# Serial_CAN_FD.net
KiCad netlist of a schematic drawn in EAGLE
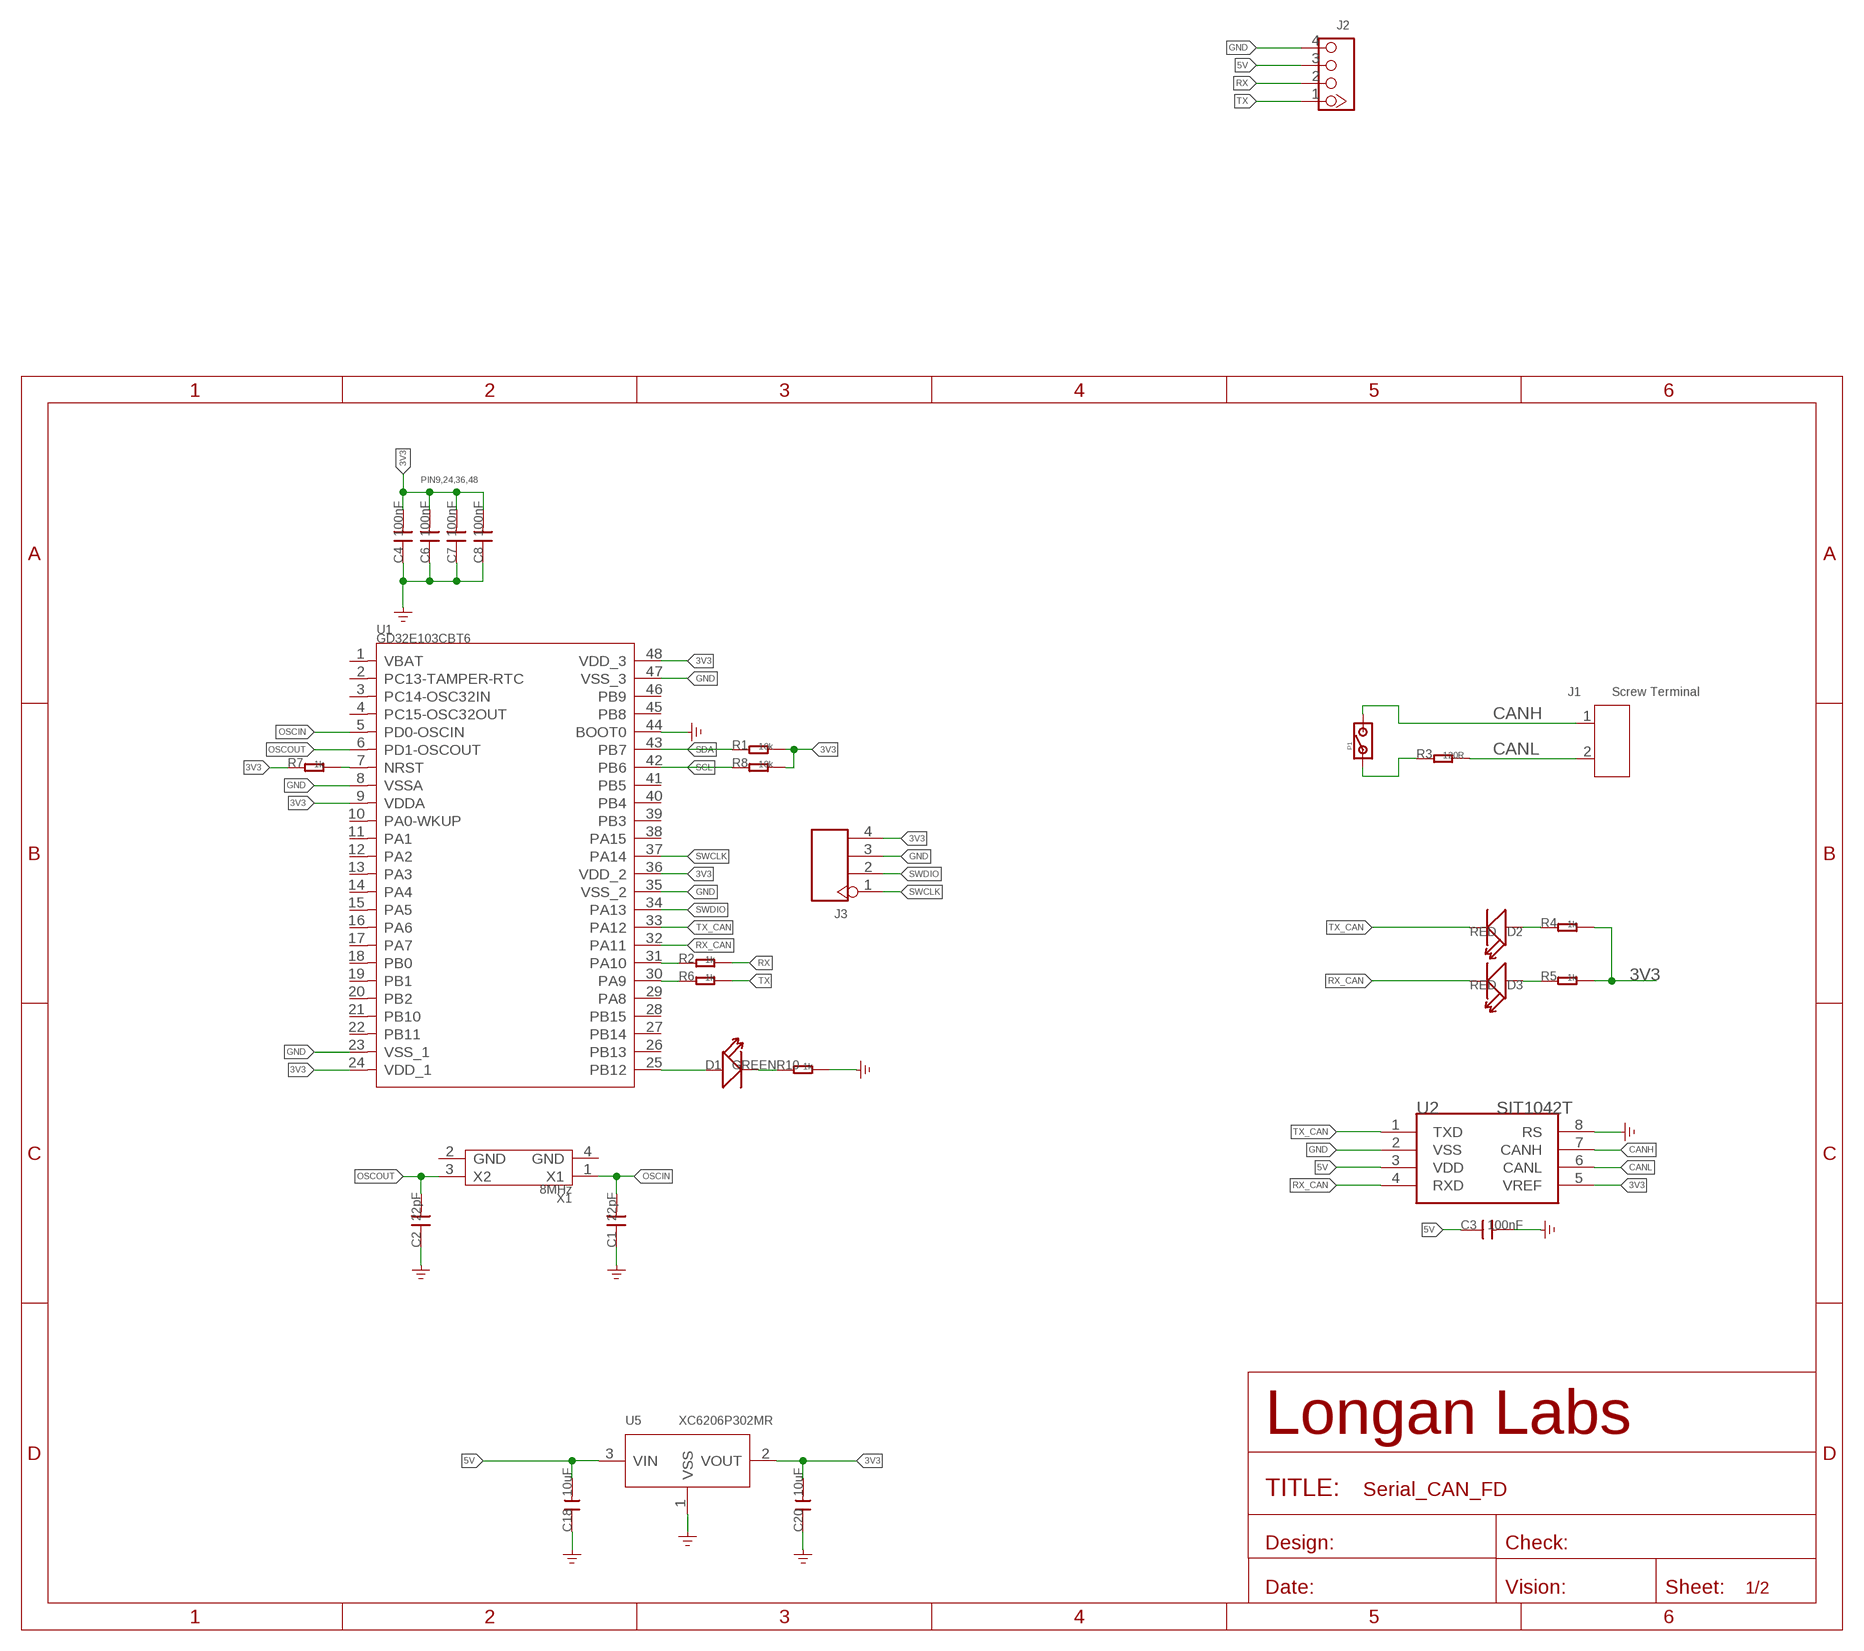
[diagram p0: schematic, sheet 1]

(export (version "E")
  (design (tool "Eeschema 10.0.6"))
  (components
    (comp (ref "C1")
      (value "22pF")
      (footprint "eagle-import:0603")
      (libsource (lib "eagle-import") (part "C-0603"))
    )
    (comp (ref "C2")
      (value "22pF")
      (footprint "eagle-import:0603")
      (libsource (lib "eagle-import") (part "C-0603"))
    )
    (comp (ref "C3")
      (value "100nF")
      (footprint "eagle-import:0603")
      (libsource (lib "eagle-import") (part "C-0603"))
    )
    (comp (ref "C4")
      (value "100nF")
      (footprint "eagle-import:0603")
      (libsource (lib "eagle-import") (part "C-0603"))
    )
    (comp (ref "C6")
      (value "100nF")
      (footprint "eagle-import:0603")
      (libsource (lib "eagle-import") (part "C-0603"))
    )
    (comp (ref "C7")
      (value "100nF")
      (footprint "eagle-import:0603")
      (libsource (lib "eagle-import") (part "C-0603"))
    )
    (comp (ref "C8")
      (value "100nF")
      (footprint "eagle-import:0603")
      (libsource (lib "eagle-import") (part "C-0603"))
    )
    (comp (ref "C18")
      (value "10uF")
      (footprint "eagle-import:C0603")
      (libsource (lib "eagle-import") (part "CAP-0603"))
    )
    (comp (ref "C20")
      (value "10uF")
      (footprint "eagle-import:C0603")
      (libsource (lib "eagle-import") (part "CAP-0603"))
    )
    (comp (ref "D1")
      (value "GREEN")
      (footprint "eagle-import:LED-0603")
      (libsource (lib "eagle-import") (part "LED'0603'"))
    )
    (comp (ref "D2")
      (value "RED")
      (footprint "eagle-import:LED-0603")
      (libsource (lib "eagle-import") (part "LED'0603'"))
    )
    (comp (ref "D3")
      (value "RED")
      (footprint "eagle-import:LED-0603")
      (libsource (lib "eagle-import") (part "LED'0603'"))
    )
    (comp (ref "J1")
      (value "Screw Terminal")
      (footprint "eagle-import:2P-3.5")
      (libsource (lib "eagle-import") (part "SCREW-TERMINAL-2P'3.5'"))
    )
    (comp (ref "J2")
      (value "320110033")
      (footprint "eagle-import:HW4-2.0")
      (libsource (lib "eagle-import") (part "GROVE-CONNECTOR-DIP-320110033"))
    )
    (comp (ref "J3")
      (value "HEADER-4P-65/35MIL")
      (footprint "eagle-import:H4-2.54")
      (libsource (lib "eagle-import") (part "HEADER-4P-65/35MIL"))
    )
    (comp (ref "P1")
      (value "PAD-JUMPER-2P")
      (footprint "eagle-import:2P-SMD-1.78X1.27")
      (libsource (lib "eagle-import") (part "PAD-JUMPER-2P"))
    )
    (comp (ref "R1")
      (value "10k")
      (footprint "eagle-import:0603")
      (libsource (lib "eagle-import") (part "R-0603"))
    )
    (comp (ref "R2")
      (value "1k")
      (footprint "eagle-import:0603")
      (libsource (lib "eagle-import") (part "R-0603"))
    )
    (comp (ref "R3")
      (value "120R")
      (footprint "eagle-import:0603")
      (libsource (lib "eagle-import") (part "R-0603"))
    )
    (comp (ref "R4")
      (value "1k")
      (footprint "eagle-import:0603")
      (libsource (lib "eagle-import") (part "R-0603"))
    )
    (comp (ref "R5")
      (value "1k")
      (footprint "eagle-import:0603")
      (libsource (lib "eagle-import") (part "R-0603"))
    )
    (comp (ref "R6")
      (value "1k")
      (footprint "eagle-import:0603")
      (libsource (lib "eagle-import") (part "R-0603"))
    )
    (comp (ref "R7")
      (value "1k")
      (footprint "eagle-import:0603")
      (libsource (lib "eagle-import") (part "R-0603"))
    )
    (comp (ref "R8")
      (value "10k")
      (footprint "eagle-import:0603")
      (libsource (lib "eagle-import") (part "R-0603"))
    )
    (comp (ref "R10")
      (value "1k")
      (footprint "eagle-import:0603")
      (libsource (lib "eagle-import") (part "R-0603"))
    )
    (comp (ref "U1")
      (value "GD32E103CBT6")
      (footprint "eagle-import:LQFP48")
      (libsource (lib "eagle-import") (part "MCU-GD32E103CBT6"))
    )
    (comp (ref "U2")
      (value "SIT1042T")
      (footprint "eagle-import:SOIC8-6.0")
      (libsource (lib "eagle-import") (part "MCP2551-SOIC8"))
    )
    (comp (ref "U5")
      (value "XC6206P302MR")
      (footprint "eagle-import:SOT-23")
      (libsource (lib "eagle-import") (part "PMIC-XC6206PMR"))
    )
    (comp (ref "X1")
      (value "8MHz")
      (footprint "eagle-import:X4-SMD-3.2X2.5X0.7MM")
      (libsource (lib "eagle-import") (part "CRYSTAL-4P-3225"))
    )
  )
  (nets
    (net (code "1") (name "3V3") (class "Default")
      (node (ref "C20") (pin "2") (pinfunction "2_2") (pintype "passive"))
      (node (ref "C4") (pin "2") (pinfunction "2_2") (pintype "passive"))
      (node (ref "C6") (pin "2") (pinfunction "2_2") (pintype "passive"))
      (node (ref "C7") (pin "2") (pinfunction "2_2") (pintype "passive"))
      (node (ref "C8") (pin "2") (pinfunction "2_2") (pintype "passive"))
      (node (ref "J3") (pin "4") (pinfunction "P$4_4") (pintype "bidirectional"))
      (node (ref "R1") (pin "2") (pinfunction "2_2") (pintype "passive"))
      (node (ref "R4") (pin "2") (pinfunction "2_2") (pintype "passive"))
      (node (ref "R5") (pin "2") (pinfunction "2_2") (pintype "passive"))
      (node (ref "R7") (pin "1") (pinfunction "1_1") (pintype "passive"))
      (node (ref "R8") (pin "2") (pinfunction "2_2") (pintype "passive"))
      (node (ref "U1") (pin "24") (pinfunction "VDD_1_24") (pintype "bidirectional"))
      (node (ref "U1") (pin "36") (pinfunction "VDD_2_36") (pintype "bidirectional"))
      (node (ref "U1") (pin "48") (pinfunction "VDD_3_48") (pintype "bidirectional"))
      (node (ref "U1") (pin "9") (pinfunction "VDDA_9") (pintype "bidirectional"))
      (node (ref "U2") (pin "5") (pinfunction "VREF_5") (pintype "bidirectional"))
      (node (ref "U5") (pin "2") (pinfunction "VOUT_2") (pintype "bidirectional"))
    )
    (net (code "2") (name "5V") (class "Default")
      (node (ref "C18") (pin "2") (pinfunction "2_2") (pintype "passive"))
      (node (ref "C3") (pin "1") (pinfunction "1_1") (pintype "passive"))
      (node (ref "J2") (pin "3") (pinfunction "3_3") (pintype "bidirectional"))
      (node (ref "U2") (pin "3") (pinfunction "VDD_3") (pintype "bidirectional"))
      (node (ref "U5") (pin "3") (pinfunction "VIN_3") (pintype "bidirectional"))
    )
    (net (code "3") (name "CANH") (class "Default")
      (node (ref "J1") (pin "1") (pinfunction "1_1") (pintype "bidirectional"))
      (node (ref "P1") (pin "2") (pinfunction "2_2") (pintype "bidirectional"))
      (node (ref "U2") (pin "7") (pinfunction "CANH_7") (pintype "bidirectional"))
    )
    (net (code "4") (name "CANL") (class "Default")
      (node (ref "J1") (pin "2") (pinfunction "2_2") (pintype "bidirectional"))
      (node (ref "R3") (pin "2") (pinfunction "2_2") (pintype "passive"))
      (node (ref "U2") (pin "6") (pinfunction "CANL_6") (pintype "bidirectional"))
    )
    (net (code "5") (name "GND") (class "Default")
      (node (ref "C1") (pin "1") (pinfunction "1_1") (pintype "passive"))
      (node (ref "C18") (pin "1") (pinfunction "1_1") (pintype "passive"))
      (node (ref "C2") (pin "1") (pinfunction "1_1") (pintype "passive"))
      (node (ref "C20") (pin "1") (pinfunction "1_1") (pintype "passive"))
      (node (ref "C3") (pin "2") (pinfunction "2_2") (pintype "passive"))
      (node (ref "C4") (pin "1") (pinfunction "1_1") (pintype "passive"))
      (node (ref "C6") (pin "1") (pinfunction "1_1") (pintype "passive"))
      (node (ref "C7") (pin "1") (pinfunction "1_1") (pintype "passive"))
      (node (ref "C8") (pin "1") (pinfunction "1_1") (pintype "passive"))
      (node (ref "J2") (pin "4") (pinfunction "4_4") (pintype "bidirectional"))
      (node (ref "J3") (pin "3") (pinfunction "P$3_3") (pintype "bidirectional"))
      (node (ref "R10") (pin "2") (pinfunction "2_2") (pintype "passive"))
      (node (ref "U1") (pin "23") (pinfunction "VSS_1_23") (pintype "bidirectional"))
      (node (ref "U1") (pin "35") (pinfunction "VSS_2_35") (pintype "bidirectional"))
      (node (ref "U1") (pin "44") (pinfunction "BOOT0_44") (pintype "bidirectional"))
      (node (ref "U1") (pin "47") (pinfunction "VSS_3_47") (pintype "bidirectional"))
      (node (ref "U1") (pin "8") (pinfunction "VSSA_8") (pintype "bidirectional"))
      (node (ref "U2") (pin "2") (pinfunction "VSS_2") (pintype "bidirectional"))
      (node (ref "U2") (pin "8") (pinfunction "RS_8") (pintype "bidirectional"))
      (node (ref "U5") (pin "1") (pinfunction "VSS_1") (pintype "bidirectional"))
    )
    (net (code "6") (name "Net-(D1-Pad-)") (class "Default")
      (node (ref "D1") (pin "-") (pinfunction "-_-") (pintype "passive"))
      (node (ref "R10") (pin "1") (pinfunction "1_1") (pintype "passive"))
    )
    (net (code "7") (name "Net-(D2-Pad+)") (class "Default")
      (node (ref "D2") (pin "+") (pinfunction "+_+") (pintype "passive"))
      (node (ref "R4") (pin "1") (pinfunction "1_1") (pintype "passive"))
    )
    (net (code "8") (name "Net-(D3-Pad+)") (class "Default")
      (node (ref "D3") (pin "+") (pinfunction "+_+") (pintype "passive"))
      (node (ref "R5") (pin "1") (pinfunction "1_1") (pintype "passive"))
    )
    (net (code "9") (name "Net-(P1-Pad1)") (class "Default")
      (node (ref "P1") (pin "1") (pinfunction "1_1") (pintype "bidirectional"))
      (node (ref "R3") (pin "1") (pinfunction "1_1") (pintype "passive"))
    )
    (net (code "10") (name "Net-(U1-NRST)") (class "Default")
      (node (ref "R7") (pin "2") (pinfunction "2_2") (pintype "passive"))
      (node (ref "U1") (pin "7") (pinfunction "NRST_7") (pintype "bidirectional"))
    )
    (net (code "11") (name "Net-(U1-PA9)") (class "Default")
      (node (ref "R6") (pin "1") (pinfunction "1_1") (pintype "passive"))
      (node (ref "U1") (pin "30") (pinfunction "PA9_30") (pintype "bidirectional"))
    )
    (net (code "12") (name "Net-(U1-PA10)") (class "Default")
      (node (ref "R2") (pin "1") (pinfunction "1_1") (pintype "passive"))
      (node (ref "U1") (pin "31") (pinfunction "PA10_31") (pintype "bidirectional"))
    )
    (net (code "13") (name "Net-(U1-PB12)") (class "Default")
      (node (ref "D1") (pin "+") (pinfunction "+_+") (pintype "passive"))
      (node (ref "U1") (pin "25") (pinfunction "PB12_25") (pintype "bidirectional"))
    )
    (net (code "14") (name "OSCIN") (class "Default")
      (node (ref "C1") (pin "2") (pinfunction "2_2") (pintype "passive"))
      (node (ref "U1") (pin "5") (pinfunction "PD0-OSCIN_5") (pintype "bidirectional"))
      (node (ref "X1") (pin "1") (pinfunction "X1_1") (pintype "bidirectional"))
    )
    (net (code "15") (name "OSCOUT") (class "Default")
      (node (ref "C2") (pin "2") (pinfunction "2_2") (pintype "passive"))
      (node (ref "U1") (pin "6") (pinfunction "PD1-OSCOUT_6") (pintype "bidirectional"))
      (node (ref "X1") (pin "3") (pinfunction "X2_3") (pintype "bidirectional"))
    )
    (net (code "16") (name "RX") (class "Default")
      (node (ref "J2") (pin "2") (pinfunction "2_2") (pintype "bidirectional"))
      (node (ref "R2") (pin "2") (pinfunction "2_2") (pintype "passive"))
    )
    (net (code "17") (name "RX_CAN") (class "Default")
      (node (ref "D3") (pin "-") (pinfunction "-_-") (pintype "passive"))
      (node (ref "U1") (pin "32") (pinfunction "PA11_32") (pintype "bidirectional"))
      (node (ref "U2") (pin "4") (pinfunction "RXD_4") (pintype "bidirectional"))
    )
    (net (code "18") (name "SCL") (class "Default")
      (node (ref "R8") (pin "1") (pinfunction "1_1") (pintype "passive"))
      (node (ref "U1") (pin "42") (pinfunction "PB6_42") (pintype "bidirectional"))
    )
    (net (code "19") (name "SDA") (class "Default")
      (node (ref "R1") (pin "1") (pinfunction "1_1") (pintype "passive"))
      (node (ref "U1") (pin "43") (pinfunction "PB7_43") (pintype "bidirectional"))
    )
    (net (code "20") (name "SWCLK") (class "Default")
      (node (ref "J3") (pin "1") (pinfunction "P$1_1") (pintype "bidirectional"))
      (node (ref "U1") (pin "37") (pinfunction "PA14_37") (pintype "bidirectional"))
    )
    (net (code "21") (name "SWDIO") (class "Default")
      (node (ref "J3") (pin "2") (pinfunction "P$2_2") (pintype "bidirectional"))
      (node (ref "U1") (pin "34") (pinfunction "PA13_34") (pintype "bidirectional"))
    )
    (net (code "22") (name "TX") (class "Default")
      (node (ref "J2") (pin "1") (pinfunction "1_1") (pintype "bidirectional"))
      (node (ref "R6") (pin "2") (pinfunction "2_2") (pintype "passive"))
    )
    (net (code "23") (name "TX_CAN") (class "Default")
      (node (ref "D2") (pin "-") (pinfunction "-_-") (pintype "passive"))
      (node (ref "U1") (pin "33") (pinfunction "PA12_33") (pintype "bidirectional"))
      (node (ref "U2") (pin "1") (pinfunction "TXD_1") (pintype "bidirectional"))
    )
    (net (code "24") (name "unconnected-(U1-PA0-WKUP-Pad10)") (class "Default")
      (node (ref "U1") (pin "10") (pinfunction "PA0-WKUP_10") (pintype "bidirectional"))
    )
    (net (code "25") (name "unconnected-(U1-PA1-Pad11)") (class "Default")
      (node (ref "U1") (pin "11") (pinfunction "PA1_11") (pintype "bidirectional"))
    )
    (net (code "26") (name "unconnected-(U1-PA2-Pad12)") (class "Default")
      (node (ref "U1") (pin "12") (pinfunction "PA2_12") (pintype "bidirectional"))
    )
    (net (code "27") (name "unconnected-(U1-PA3-Pad13)") (class "Default")
      (node (ref "U1") (pin "13") (pinfunction "PA3_13") (pintype "bidirectional"))
    )
    (net (code "28") (name "unconnected-(U1-PA4-Pad14)") (class "Default")
      (node (ref "U1") (pin "14") (pinfunction "PA4_14") (pintype "bidirectional"))
    )
    (net (code "29") (name "unconnected-(U1-PA5-Pad15)") (class "Default")
      (node (ref "U1") (pin "15") (pinfunction "PA5_15") (pintype "bidirectional"))
    )
    (net (code "30") (name "unconnected-(U1-PA6-Pad16)") (class "Default")
      (node (ref "U1") (pin "16") (pinfunction "PA6_16") (pintype "bidirectional"))
    )
    (net (code "31") (name "unconnected-(U1-PA7-Pad17)") (class "Default")
      (node (ref "U1") (pin "17") (pinfunction "PA7_17") (pintype "bidirectional"))
    )
    (net (code "32") (name "unconnected-(U1-PA8-Pad29)") (class "Default")
      (node (ref "U1") (pin "29") (pinfunction "PA8_29") (pintype "bidirectional"))
    )
    (net (code "33") (name "unconnected-(U1-PA15-Pad38)") (class "Default")
      (node (ref "U1") (pin "38") (pinfunction "PA15_38") (pintype "bidirectional"))
    )
    (net (code "34") (name "unconnected-(U1-PB0-Pad18)") (class "Default")
      (node (ref "U1") (pin "18") (pinfunction "PB0_18") (pintype "bidirectional"))
    )
    (net (code "35") (name "unconnected-(U1-PB1-Pad19)") (class "Default")
      (node (ref "U1") (pin "19") (pinfunction "PB1_19") (pintype "bidirectional"))
    )
    (net (code "36") (name "unconnected-(U1-PB2-Pad20)") (class "Default")
      (node (ref "U1") (pin "20") (pinfunction "PB2_20") (pintype "bidirectional"))
    )
    (net (code "37") (name "unconnected-(U1-PB3-Pad39)") (class "Default")
      (node (ref "U1") (pin "39") (pinfunction "PB3_39") (pintype "bidirectional"))
    )
    (net (code "38") (name "unconnected-(U1-PB4-Pad40)") (class "Default")
      (node (ref "U1") (pin "40") (pinfunction "PB4_40") (pintype "bidirectional"))
    )
    (net (code "39") (name "unconnected-(U1-PB5-Pad41)") (class "Default")
      (node (ref "U1") (pin "41") (pinfunction "PB5_41") (pintype "bidirectional"))
    )
    (net (code "40") (name "unconnected-(U1-PB8-Pad45)") (class "Default")
      (node (ref "U1") (pin "45") (pinfunction "PB8_45") (pintype "bidirectional"))
    )
    (net (code "41") (name "unconnected-(U1-PB9-Pad46)") (class "Default")
      (node (ref "U1") (pin "46") (pinfunction "PB9_46") (pintype "bidirectional"))
    )
    (net (code "42") (name "unconnected-(U1-PB10-Pad21)") (class "Default")
      (node (ref "U1") (pin "21") (pinfunction "PB10_21") (pintype "bidirectional"))
    )
    (net (code "43") (name "unconnected-(U1-PB11-Pad22)") (class "Default")
      (node (ref "U1") (pin "22") (pinfunction "PB11_22") (pintype "bidirectional"))
    )
    (net (code "44") (name "unconnected-(U1-PB13-Pad26)") (class "Default")
      (node (ref "U1") (pin "26") (pinfunction "PB13_26") (pintype "bidirectional"))
    )
    (net (code "45") (name "unconnected-(U1-PB14-Pad27)") (class "Default")
      (node (ref "U1") (pin "27") (pinfunction "PB14_27") (pintype "bidirectional"))
    )
    (net (code "46") (name "unconnected-(U1-PB15-Pad28)") (class "Default")
      (node (ref "U1") (pin "28") (pinfunction "PB15_28") (pintype "bidirectional"))
    )
    (net (code "47") (name "unconnected-(U1-PC13-TAMPER-RTC-Pad2)") (class "Default")
      (node (ref "U1") (pin "2") (pinfunction "PC13-TAMPER-RTC_2") (pintype "bidirectional"))
    )
    (net (code "48") (name "unconnected-(U1-PC14-OSC32IN-Pad3)") (class "Default")
      (node (ref "U1") (pin "3") (pinfunction "PC14-OSC32IN_3") (pintype "bidirectional"))
    )
    (net (code "49") (name "unconnected-(U1-PC15-OSC32OUT-Pad4)") (class "Default")
      (node (ref "U1") (pin "4") (pinfunction "PC15-OSC32OUT_4") (pintype "bidirectional"))
    )
    (net (code "50") (name "unconnected-(U1-VBAT-Pad1)") (class "Default")
      (node (ref "U1") (pin "1") (pinfunction "VBAT_1") (pintype "bidirectional"))
    )
    (net (code "51") (name "unconnected-(X1-GND-Pad2)") (class "Default")
      (node (ref "X1") (pin "2") (pinfunction "GND_2") (pintype "bidirectional"))
    )
    (net (code "52") (name "unconnected-(X1-GND-Pad4)") (class "Default")
      (node (ref "X1") (pin "4") (pinfunction "GND_4") (pintype "bidirectional"))
    )
  )
)
